# OneBellInterfaceRevB.net
KiCad netlist of a schematic drawn in EAGLE
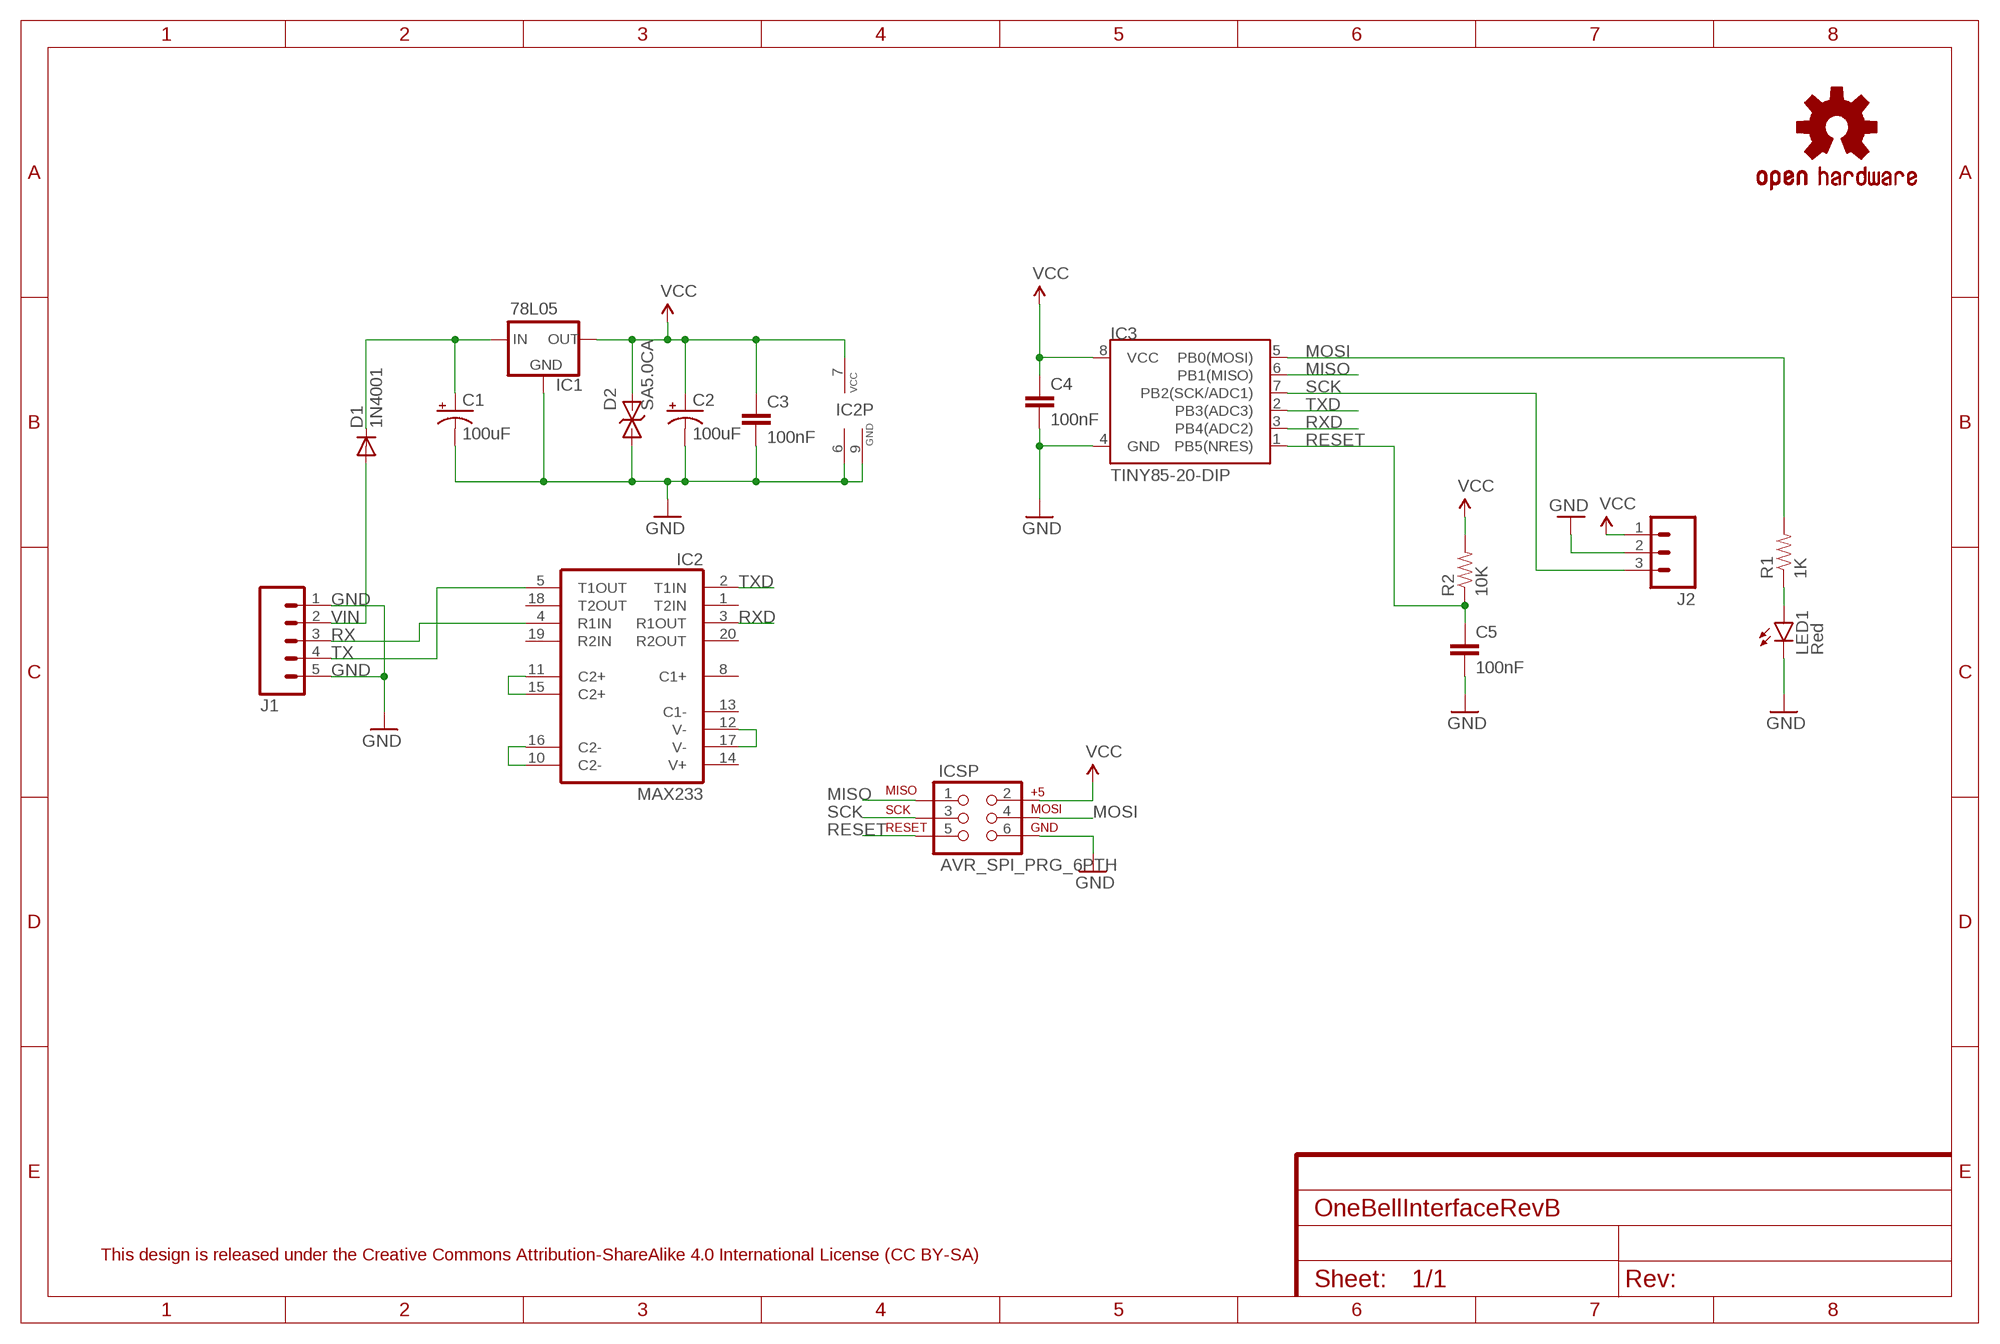
[diagram p0: schematic, sheet 1]

(export (version "E")
  (design (tool "Eeschema 10.0.6"))
  (components
    (comp (ref "C1")
      (value "100uF")
      (footprint "eagle-import:CPOL-RADIAL-100UF-25V")
      (libsource (lib "eagle-import") (part "CAP_POLPTH1"))
    )
    (comp (ref "C2")
      (value "100uF")
      (footprint "eagle-import:CPOL-RADIAL-100UF-25V")
      (libsource (lib "eagle-import") (part "CAP_POLPTH1"))
    )
    (comp (ref "C3")
      (value "100nF")
      (footprint "eagle-import:CAP-PTH-SMALL")
      (libsource (lib "eagle-import") (part "CAPPTH"))
    )
    (comp (ref "C4")
      (value "100nF")
      (footprint "eagle-import:CAP-PTH-SMALL")
      (libsource (lib "eagle-import") (part "CAPPTH"))
    )
    (comp (ref "C5")
      (value "100nF")
      (footprint "eagle-import:CAP-PTH-SMALL")
      (libsource (lib "eagle-import") (part "CAPPTH"))
    )
    (comp (ref "D1")
      (value "1N4001")
      (footprint "eagle-import:DO41_DIODE")
      (libsource (lib "eagle-import") (part "1N4001"))
    )
    (comp (ref "D2")
      (value "SA5.0CA")
      (footprint "eagle-import:DO41_TVS")
      (libsource (lib "eagle-import") (part "SA5.0CA"))
    )
    (comp (ref "IC1")
      (value "78L05")
      (footprint "eagle-import:TO-92")
      (libsource (lib "eagle-import") (part "V_REG_78XXTO-92_UNTESTED"))
    )
    (comp (ref "IC2")
      (value "MAX233")
      (footprint "eagle-import:DIL20")
      (fields (field (name "MPN") "MAX233ACPP+G36"))
      (libsource (lib "eagle-import") (part "MAX233"))
    )
    (comp (ref "IC3")
      (value "TINY85-20-DIP")
      (footprint "eagle-import:DIL08")
      (libsource (lib "eagle-import") (part "ATTINY45DIL08_LONG_PADS"))
    )
    (comp (ref "ICSP")
      (value "AVR_SPI_PRG_6PTH")
      (footprint "eagle-import:2X3")
      (libsource (lib "eagle-import") (part "AVR_SPI_PRG_6PTH"))
    )
    (comp (ref "J1")
      (value "M05PTH")
      (footprint "eagle-import:1X05")
      (libsource (lib "eagle-import") (part "M05PTH"))
    )
    (comp (ref "J2")
      (value "M03PTH")
      (footprint "eagle-import:1X03")
      (libsource (lib "eagle-import") (part "M03PTH"))
    )
    (comp (ref "LED1")
      (value "Red")
      (footprint "eagle-import:LED3MM")
      (libsource (lib "eagle-import") (part "LED3MM"))
    )
    (comp (ref "LOGO1")
      (value "OSHW-LOGOS")
      (footprint "eagle-import:OSHW-LOGO-S")
      (libsource (lib "eagle-import") (part "OSHW-LOGOS"))
    )
    (comp (ref "R1")
      (value "1K")
      (footprint "eagle-import:AXIAL-0.4")
      (libsource (lib "eagle-import") (part "RESISTORPTH-1/4W"))
    )
    (comp (ref "R2")
      (value "10K")
      (footprint "eagle-import:AXIAL-0.4")
      (libsource (lib "eagle-import") (part "RESISTORPTH-1/4W"))
    )
  )
  (nets
    (net (code "1") (name "/MISO") (class "Default")
      (node (ref "IC3") (pin "6") (pinfunction "PB1(MISO)_6") (pintype "bidirectional"))
      (node (ref "ICSP") (pin "1") (pinfunction "1_1") (pintype "passive"))
    )
    (net (code "2") (name "/MOSI") (class "Default")
      (node (ref "IC3") (pin "5") (pinfunction "PB0(MOSI)_5") (pintype "bidirectional"))
      (node (ref "ICSP") (pin "4") (pinfunction "4_4") (pintype "passive"))
      (node (ref "R1") (pin "P$2") (pinfunction "2_P$2") (pintype "passive"))
    )
    (net (code "3") (name "/RESET") (class "Default")
      (node (ref "C5") (pin "1") (pinfunction "1_1") (pintype "passive"))
      (node (ref "IC3") (pin "1") (pinfunction "PB5(NRES)_1") (pintype "bidirectional"))
      (node (ref "ICSP") (pin "5") (pinfunction "5_5") (pintype "passive"))
      (node (ref "R2") (pin "P$1") (pinfunction "1_P$1") (pintype "passive"))
    )
    (net (code "4") (name "/RX") (class "Default")
      (node (ref "IC2") (pin "4") (pinfunction "R1IN_4") (pintype "input"))
      (node (ref "J1") (pin "3") (pinfunction "3_3") (pintype "passive"))
    )
    (net (code "5") (name "/RXD") (class "Default")
      (node (ref "IC2") (pin "3") (pinfunction "R1OUT_3") (pintype "output"))
      (node (ref "IC3") (pin "3") (pinfunction "PB4(ADC2)_3") (pintype "bidirectional"))
    )
    (net (code "6") (name "/SCK") (class "Default")
      (node (ref "IC3") (pin "7") (pinfunction "PB2(SCK/ADC1)_7") (pintype "bidirectional"))
      (node (ref "ICSP") (pin "3") (pinfunction "3_3") (pintype "passive"))
      (node (ref "J2") (pin "3") (pinfunction "3_3") (pintype "passive"))
    )
    (net (code "7") (name "/TX") (class "Default")
      (node (ref "IC2") (pin "5") (pinfunction "T1OUT_5") (pintype "output"))
      (node (ref "J1") (pin "4") (pinfunction "4_4") (pintype "passive"))
    )
    (net (code "8") (name "/TXD") (class "Default")
      (node (ref "IC2") (pin "2") (pinfunction "T1IN_2") (pintype "input"))
      (node (ref "IC3") (pin "2") (pinfunction "PB3(ADC3)_2") (pintype "bidirectional"))
    )
    (net (code "9") (name "/VIN") (class "Default")
      (node (ref "D1") (pin "A") (pinfunction "A_A") (pintype "passive"))
      (node (ref "J1") (pin "2") (pinfunction "2_2") (pintype "passive"))
    )
    (net (code "10") (name "GND") (class "Default")
      (node (ref "C1") (pin "2") (pinfunction "-_2") (pintype "passive"))
      (node (ref "C2") (pin "2") (pinfunction "-_2") (pintype "passive"))
      (node (ref "C3") (pin "2") (pinfunction "2_2") (pintype "passive"))
      (node (ref "C4") (pin "2") (pinfunction "2_2") (pintype "passive"))
      (node (ref "C5") (pin "2") (pinfunction "2_2") (pintype "passive"))
      (node (ref "D2") (pin "A") (pinfunction "A_A") (pintype "passive"))
      (node (ref "IC1") (pin "2") (pinfunction "GND_2") (pintype "input"))
      (node (ref "IC2") (pin "6") (pinfunction "GND_6") (pintype "power_in"))
      (node (ref "IC2") (pin "9") (pinfunction "GND_9") (pintype "power_in"))
      (node (ref "IC3") (pin "4") (pinfunction "GND_4") (pintype "bidirectional"))
      (node (ref "ICSP") (pin "6") (pinfunction "6_6") (pintype "passive"))
      (node (ref "J1") (pin "1") (pinfunction "1_1") (pintype "passive"))
      (node (ref "J1") (pin "5") (pinfunction "5_5") (pintype "passive"))
      (node (ref "J2") (pin "2") (pinfunction "2_2") (pintype "passive"))
      (node (ref "LED1") (pin "K") (pinfunction "C_K") (pintype "passive"))
    )
    (net (code "11") (name "Net-(C1-+)") (class "Default")
      (node (ref "C1") (pin "1") (pinfunction "+_1") (pintype "passive"))
      (node (ref "D1") (pin "C") (pinfunction "C_C") (pintype "passive"))
      (node (ref "IC1") (pin "3") (pinfunction "IN_3") (pintype "input"))
    )
    (net (code "12") (name "Net-(IC2A-C2+-Pad11)") (class "Default")
      (node (ref "IC2") (pin "11") (pinfunction "C2+_11") (pintype "bidirectional"))
      (node (ref "IC2") (pin "15") (pinfunction "C2+_15") (pintype "bidirectional"))
    )
    (net (code "13") (name "Net-(IC2A-C2--Pad10)") (class "Default")
      (node (ref "IC2") (pin "10") (pinfunction "C2-_10") (pintype "bidirectional"))
      (node (ref "IC2") (pin "16") (pinfunction "C2-_16") (pintype "bidirectional"))
    )
    (net (code "14") (name "Net-(IC2A-V--Pad12)") (class "Default")
      (node (ref "IC2") (pin "12") (pinfunction "V-_12") (pintype "bidirectional"))
      (node (ref "IC2") (pin "17") (pinfunction "V-_17") (pintype "bidirectional"))
    )
    (net (code "15") (name "Net-(R1-1)") (class "Default")
      (node (ref "LED1") (pin "A") (pinfunction "A_A") (pintype "passive"))
      (node (ref "R1") (pin "P$1") (pinfunction "1_P$1") (pintype "passive"))
    )
    (net (code "16") (name "VCC") (class "Default")
      (node (ref "C2") (pin "1") (pinfunction "+_1") (pintype "passive"))
      (node (ref "C3") (pin "1") (pinfunction "1_1") (pintype "passive"))
      (node (ref "C4") (pin "1") (pinfunction "1_1") (pintype "passive"))
      (node (ref "D2") (pin "C") (pinfunction "C_C") (pintype "passive"))
      (node (ref "IC1") (pin "1") (pinfunction "OUT_1") (pintype "passive"))
      (node (ref "IC2") (pin "7") (pinfunction "VCC_7") (pintype "power_in"))
      (node (ref "IC3") (pin "8") (pinfunction "VCC_8") (pintype "bidirectional"))
      (node (ref "ICSP") (pin "2") (pinfunction "2_2") (pintype "passive"))
      (node (ref "J2") (pin "1") (pinfunction "1_1") (pintype "passive"))
      (node (ref "R2") (pin "P$2") (pinfunction "2_P$2") (pintype "passive"))
    )
    (net (code "17") (name "unconnected-(IC2A-C1+-Pad8)") (class "Default")
      (node (ref "IC2") (pin "8") (pinfunction "C1+_8") (pintype "bidirectional"))
    )
    (net (code "18") (name "unconnected-(IC2A-C1--Pad13)") (class "Default")
      (node (ref "IC2") (pin "13") (pinfunction "C1-_13") (pintype "bidirectional"))
    )
    (net (code "19") (name "unconnected-(IC2A-R2IN-Pad19)") (class "Default")
      (node (ref "IC2") (pin "19") (pinfunction "R2IN_19") (pintype "input"))
    )
    (net (code "20") (name "unconnected-(IC2A-R2OUT-Pad20)") (class "Default")
      (node (ref "IC2") (pin "20") (pinfunction "R2OUT_20") (pintype "output"))
    )
    (net (code "21") (name "unconnected-(IC2A-T2IN-Pad1)") (class "Default")
      (node (ref "IC2") (pin "1") (pinfunction "T2IN_1") (pintype "input"))
    )
    (net (code "22") (name "unconnected-(IC2A-T2OUT-Pad18)") (class "Default")
      (node (ref "IC2") (pin "18") (pinfunction "T2OUT_18") (pintype "output"))
    )
    (net (code "23") (name "unconnected-(IC2A-V+-Pad14)") (class "Default")
      (node (ref "IC2") (pin "14") (pinfunction "V+_14") (pintype "bidirectional"))
    )
  )
)
